# 12_-_UARTS.net
KiCad netlist of a schematic drawn in Altium Designer
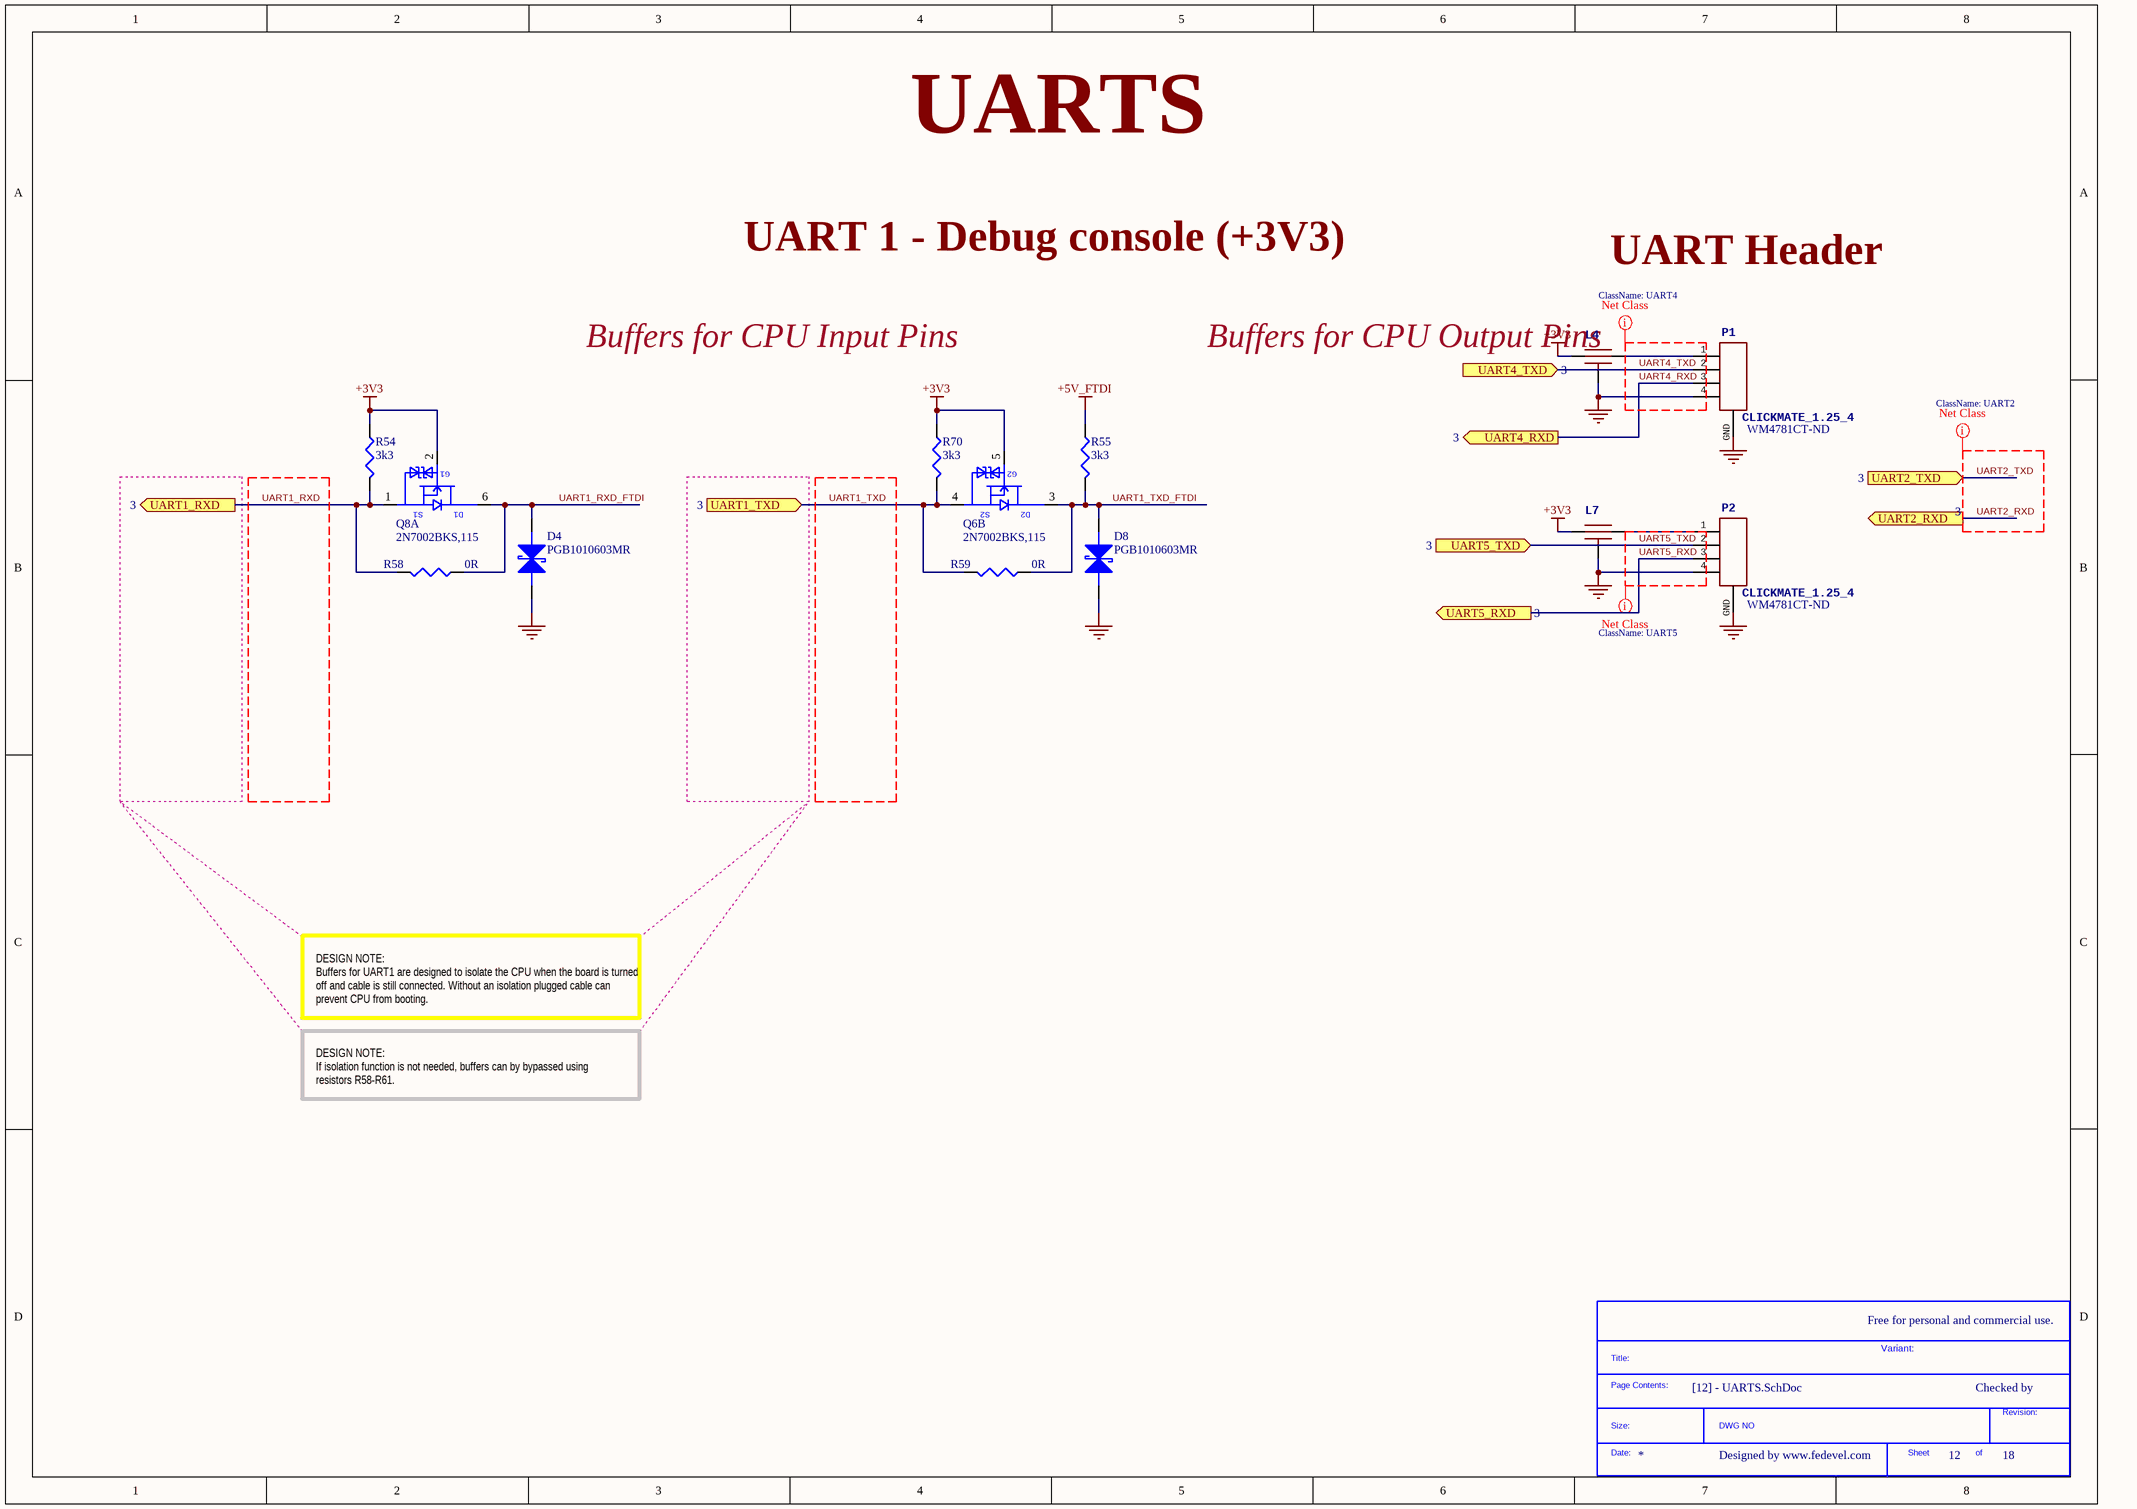
[diagram p0: [12] - UARTS.SchDoc]

(export (version "E")
  (design (tool "Eeschema 10.0.6"))
  (components
    (comp (ref "D4")
      (value "PGB1010603MR")
      (footprint "C0603")
      (description "SUPPRESSOR ESD 24VDC 0603 SMD")
      (fields (field (name "MANUFACTURER") "Littelfuse Inc") (field (name ".CREATOR") "MM"))
      (libsource (lib "Integrated_Library_FEDEVEL_APR_2015") (part "PGB1010603MR"))
    )
    (comp (ref "D8")
      (value "PGB1010603MR")
      (footprint "C0603")
      (description "SUPPRESSOR ESD 24VDC 0603 SMD")
      (fields (field (name "MANUFACTURER") "Littelfuse Inc") (field (name ".CREATOR") "MM"))
      (libsource (lib "Integrated_Library_FEDEVEL_APR_2015") (part "PGB1010603MR"))
    )
    (comp (ref "L4")
      (value "Kyocera KNH16C104DA5TS EMI filter")
      (footprint "KYOCERA-KNH16-DA")
      (description "Capacitor, Filter, 0.1uF, 25V, 2A, 0603, SMD")
      (fields (field (name "3DR_PARTNO") "ECM0719"))
      (libsource (lib "PCA_0005_FULL_CB_REV_A") (part "KNH16C104DA5TS"))
    )
    (comp (ref "L7")
      (value "Kyocera KNH16C104DA5TS EMI filter")
      (footprint "KYOCERA-KNH16-DA")
      (description "Capacitor, Filter, 0.1uF, 25V, 2A, 0603, SMD")
      (fields (field (name "3DR_PARTNO") "ECM0719"))
      (libsource (lib "PCA_0005_FULL_CB_REV_A") (part "KNH16C104DA5TS"))
    )
    (comp (ref "P1")
      (value "CLICKMATE_1.25_4")
      (footprint "CLICKMATE_V4")
      (description "Connector, Rcpt, 4Pos, 1.25MM, W/B, VERT, SMD, Tin")
      (fields (field (name "SUPPLIER PART NUMBER 1") "WM4781CT-ND") (field (name "3DR_PARTNO") "PRT0441"))
      (libsource (lib "PCA_0005_FULL_CB_REV_A") (part "CLICKMATE_1.25_4"))
    )
    (comp (ref "P2")
      (value "CLICKMATE_1.25_4")
      (footprint "CLICKMATE_V4")
      (description "Connector, Rcpt, 4Pos, 1.25MM, W/B, VERT, SMD, Tin")
      (fields (field (name "SUPPLIER PART NUMBER 1") "WM4781CT-ND") (field (name "3DR_PARTNO") "PRT0441"))
      (libsource (lib "PCA_0005_FULL_CB_REV_A") (part "CLICKMATE_1.25_4"))
    )
    (comp (ref "Q6")
      (value "2N7002BKS,115")
      (footprint "SOT363")
      (description "MOSFET 2N-CH 60V 0.3A 6TSSOP")
      (fields
        (field (name "MANUFACTURER") "NXP Semiconductors")
        (field (name ".CREATOR") "MM")
        (field (name ".CHECKED SCH") "MM")
        (field (name ".CHECKED PCB") "MM")
      )
      (libsource (lib "Integrated_Library_FEDEVEL_APR_2015") (part "2N7002BKS,115"))
    )
    (comp (ref "Q8")
      (value "2N7002BKS,115")
      (footprint "SOT363")
      (description "MOSFET 2N-CH 60V 0.3A 6TSSOP")
      (fields
        (field (name "MANUFACTURER") "NXP Semiconductors")
        (field (name ".CREATOR") "MM")
        (field (name ".CHECKED SCH") "MM")
        (field (name ".CHECKED PCB") "MM")
      )
      (libsource (lib "Integrated_Library_FEDEVEL_APR_2015") (part "2N7002BKS,115"))
    )
    (comp (ref "R54")
      (value "3k3")
      (footprint "R0402")
      (description "RES 3.30K OHM 1/16W 1% 0402 SMD")
      (fields
        (field (name "MANUFACTURER") "Yageo")
        (field (name "MANUFACTURER PART NUMBER") "RC0402FR-073K3L")
      )
      (libsource (lib "Integrated_Library_FEDEVEL_APR_2015") (part "RC0402FR-073K3L"))
    )
    (comp (ref "R55")
      (value "3k3")
      (footprint "R0402")
      (description "RES 3.30K OHM 1/16W 1% 0402 SMD")
      (fields
        (field (name "MANUFACTURER") "Yageo")
        (field (name "MANUFACTURER PART NUMBER") "RC0402FR-073K3L")
      )
      (libsource (lib "Integrated_Library_FEDEVEL_APR_2015") (part "RC0402FR-073K3L"))
    )
    (comp (ref "R58")
      (value "0R")
      (footprint "R0402")
      (description "RES 0.0 OHM 1/16W 0402 SMD")
      (fields
        (field (name "MANUFACTURER") "Yageo")
        (field (name "MANUFACTURER PART NUMBER") "RC0402JR-070RL")
      )
      (libsource (lib "Integrated_Library_FEDEVEL_APR_2015") (part "RC0402JR-070RL"))
    )
    (comp (ref "R59")
      (value "0R")
      (footprint "R0402")
      (description "RES 0.0 OHM 1/16W 0402 SMD")
      (fields
        (field (name "MANUFACTURER") "Yageo")
        (field (name "MANUFACTURER PART NUMBER") "RC0402JR-070RL")
      )
      (libsource (lib "Integrated_Library_FEDEVEL_APR_2015") (part "RC0402JR-070RL"))
    )
    (comp (ref "R70")
      (value "3k3")
      (footprint "R0402")
      (description "RES 3.30K OHM 1/16W 1% 0402 SMD")
      (fields
        (field (name "MANUFACTURER") "Yageo")
        (field (name "MANUFACTURER PART NUMBER") "RC0402FR-073K3L")
      )
      (libsource (lib "Integrated_Library_FEDEVEL_APR_2015") (part "RC0402FR-073K3L"))
    )
  )
  (nets
    (net (code "1") (name "+3V3") (class "Default")
      (node (ref "L4") (pin "P$1") (pinfunction "P$1_P$1") (pintype "passive"))
      (node (ref "L7") (pin "P$1") (pinfunction "P$1_P$1") (pintype "passive"))
      (node (ref "Q6") (pin "5") (pinfunction "GATE2_5") (pintype "passive"))
      (node (ref "Q8") (pin "2") (pinfunction "GATE1_2") (pintype "passive"))
      (node (ref "R54") (pin "2") (pinfunction "2_2") (pintype "passive"))
      (node (ref "R70") (pin "2") (pinfunction "2_2") (pintype "passive"))
    )
    (net (code "2") (name "+5V_FTDI") (class "Default")
      (node (ref "R55") (pin "2") (pinfunction "2_2") (pintype "passive"))
    )
    (net (code "3") (name "/UART1_RXD") (class "Default")
      (node (ref "Q8") (pin "1") (pinfunction "SOURCE1_1") (pintype "passive"))
      (node (ref "R54") (pin "1") (pinfunction "1_1") (pintype "passive"))
      (node (ref "R58") (pin "1") (pinfunction "1_1") (pintype "passive"))
    )
    (net (code "4") (name "/UART1_RXD_FTDI") (class "Default")
      (node (ref "D4") (pin "1") (pinfunction "1_1") (pintype "passive"))
      (node (ref "Q8") (pin "6") (pinfunction "DRAIN1_6") (pintype "passive"))
      (node (ref "R58") (pin "2") (pinfunction "2_2") (pintype "passive"))
    )
    (net (code "5") (name "/UART1_TXD") (class "Default")
      (node (ref "Q6") (pin "4") (pinfunction "SOURCE2_4") (pintype "passive"))
      (node (ref "R59") (pin "1") (pinfunction "1_1") (pintype "passive"))
      (node (ref "R70") (pin "1") (pinfunction "1_1") (pintype "passive"))
    )
    (net (code "6") (name "/UART1_TXD_FTDI") (class "Default")
      (node (ref "D8") (pin "1") (pinfunction "1_1") (pintype "passive"))
      (node (ref "Q6") (pin "3") (pinfunction "DRAIN2_3") (pintype "passive"))
      (node (ref "R55") (pin "1") (pinfunction "1_1") (pintype "passive"))
      (node (ref "R59") (pin "2") (pinfunction "2_2") (pintype "passive"))
    )
    (net (code "9") (name "/UART4_RXD") (class "Default")
      (node (ref "P1") (pin "3") (pinfunction "3_3") (pintype "passive"))
    )
    (net (code "10") (name "/UART4_TXD") (class "Default")
      (node (ref "P1") (pin "2") (pinfunction "2_2") (pintype "passive"))
    )
    (net (code "11") (name "/UART5_RXD") (class "Default")
      (node (ref "P2") (pin "3") (pinfunction "3_3") (pintype "passive"))
    )
    (net (code "12") (name "/UART5_TXD") (class "Default")
      (node (ref "P2") (pin "2") (pinfunction "2_2") (pintype "passive"))
    )
    (net (code "13") (name "GND") (class "Default")
      (node (ref "D4") (pin "2") (pinfunction "2_2") (pintype "passive"))
      (node (ref "D8") (pin "2") (pinfunction "2_2") (pintype "passive"))
      (node (ref "L4") (pin "GND") (pinfunction "GND_GND") (pintype "passive"))
      (node (ref "L7") (pin "GND") (pinfunction "GND_GND") (pintype "passive"))
      (node (ref "P1") (pin "4") (pinfunction "4_4") (pintype "passive"))
      (node (ref "P1") (pin "GND") (pinfunction "GND_GND") (pintype "passive"))
      (node (ref "P2") (pin "4") (pinfunction "4_4") (pintype "passive"))
      (node (ref "P2") (pin "GND") (pinfunction "GND_GND") (pintype "passive"))
    )
    (net (code "14") (name "Net-(L4-PadP$2)") (class "Default")
      (node (ref "L4") (pin "P$2") (pinfunction "P$2_P$2") (pintype "passive"))
      (node (ref "P1") (pin "1") (pinfunction "1_1") (pintype "passive"))
    )
    (net (code "15") (name "Net-(L7-PadP$2)") (class "Default")
      (node (ref "L7") (pin "P$2") (pinfunction "P$2_P$2") (pintype "passive"))
      (node (ref "P2") (pin "1") (pinfunction "1_1") (pintype "passive"))
    )
  )
)
